# Power_Supplies.net
KiCad netlist of a schematic drawn in Altium Designer
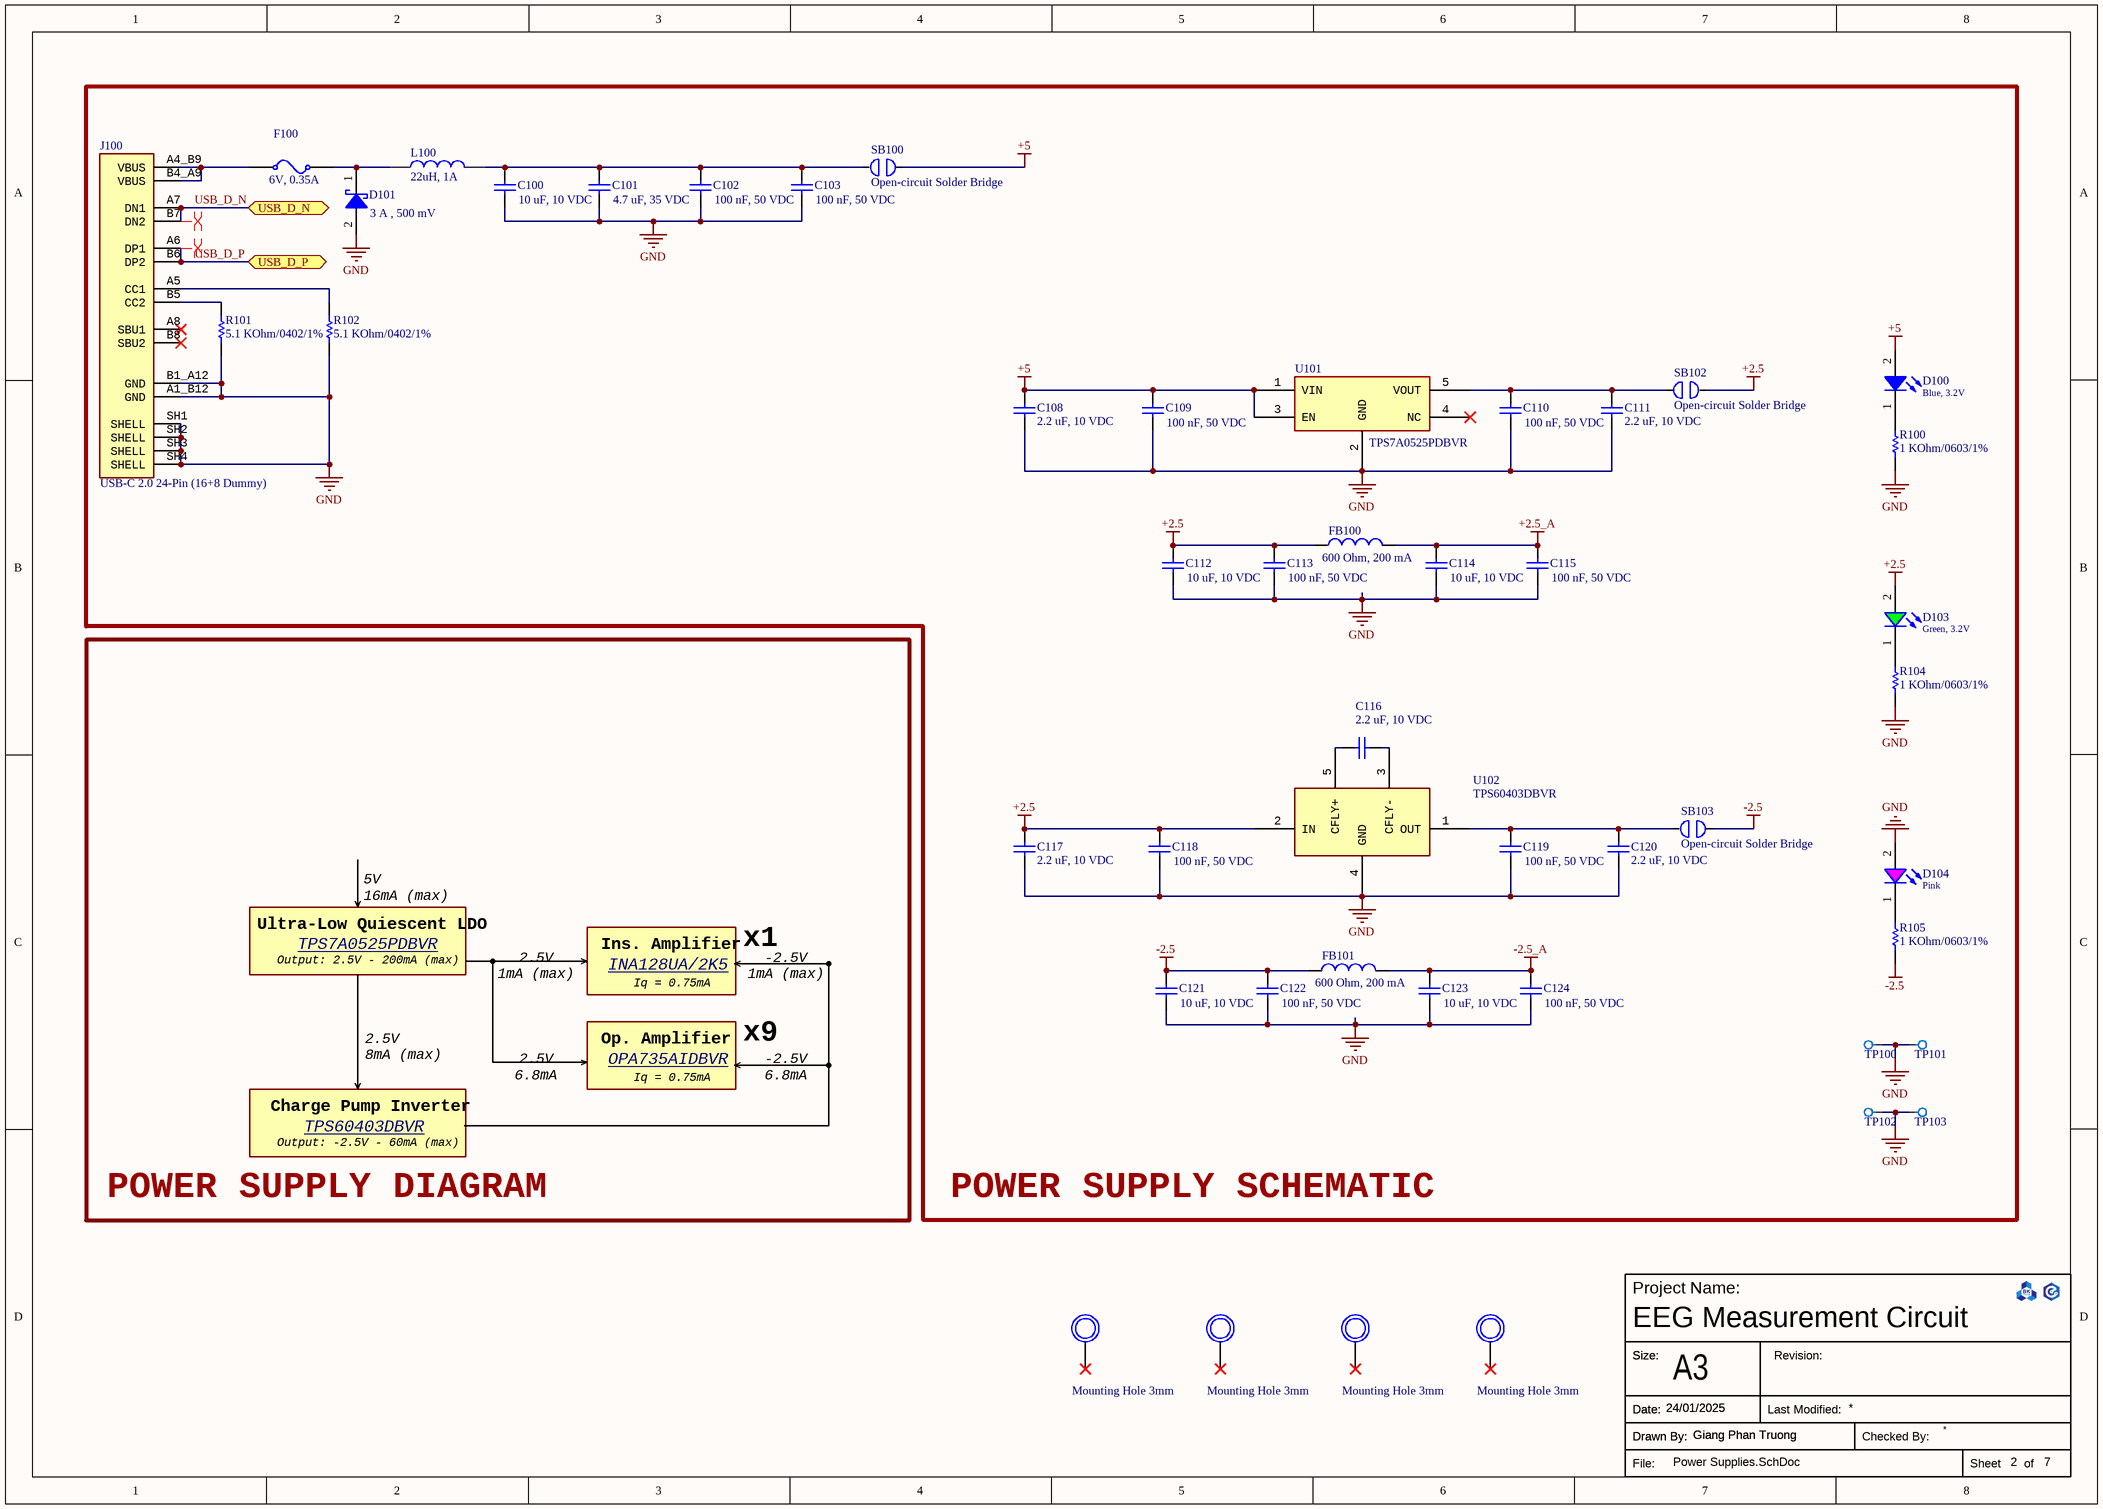
[diagram p0: Power Supplies.SchDoc]

(export (version "E")
  (design (tool "Eeschema 10.0.6"))
  (components
    (comp (ref "C100")
      (value "10 uF, 10 VDC")
      (footprint "CAP_0603")
      (description "CAP, size 0603, 10 uF, 10 VDC")
      (fields (field (name "TOLERANCE") "+/-10%"))
      (libsource (lib "Altium_Ceramic_Cap") (part "0106031061010"))
    )
    (comp (ref "C101")
      (value "4.7 uF, 35 VDC")
      (footprint "CAP_0603")
      (description "CAP, size 0603, 4.7 uF, 35 VDC")
      (fields (field (name "TOLERANCE") "+/-10%"))
      (libsource (lib "Altium_Ceramic_Cap") (part "0106034751035"))
    )
    (comp (ref "C102")
      (value "100 nF, 50 VDC")
      (footprint "CAP_0603")
      (description "CAP, size 0603, 100 nF, 50 VDC")
      (fields (field (name "TOLERANCE") "+/-10%"))
      (libsource (lib "Altium_Ceramic_Cap") (part "0106031041050"))
    )
    (comp (ref "C103")
      (value "100 nF, 50 VDC")
      (footprint "CAP_0603")
      (description "CAP, size 0603, 100 nF, 50 VDC")
      (fields (field (name "TOLERANCE") "+/-10%"))
      (libsource (lib "Altium_Ceramic_Cap") (part "0106031041050"))
    )
    (comp (ref "C108")
      (value "2.2 uF, 10 VDC")
      (footprint "CAP_0603")
      (description "CAP, size 0603, 2.2 uF, 10 VDC")
      (fields (field (name "TOLERANCE") "+/-10%"))
      (libsource (lib "Altium_Ceramic_Cap") (part "0106032251010"))
    )
    (comp (ref "C109")
      (value "100 nF, 50 VDC")
      (footprint "CAP_0603")
      (description "CAP, size 0603, 100 nF, 50 VDC")
      (fields (field (name "TOLERANCE") "+/-10%"))
      (libsource (lib "Altium_Ceramic_Cap") (part "0106031041050"))
    )
    (comp (ref "C110")
      (value "100 nF, 50 VDC")
      (footprint "CAP_0603")
      (description "CAP, size 0603, 100 nF, 50 VDC")
      (fields (field (name "TOLERANCE") "+/-10%"))
      (libsource (lib "Altium_Ceramic_Cap") (part "0106031041050"))
    )
    (comp (ref "C111")
      (value "2.2 uF, 10 VDC")
      (footprint "CAP_0603")
      (description "CAP, size 0603, 2.2 uF, 10 VDC")
      (fields (field (name "TOLERANCE") "+/-10%"))
      (libsource (lib "Altium_Ceramic_Cap") (part "0106032251010"))
    )
    (comp (ref "C112")
      (value "10 uF, 10 VDC")
      (footprint "CAP_0603")
      (description "CAP, size 0603, 10 uF, 10 VDC")
      (fields (field (name "TOLERANCE") "+/-10%"))
      (libsource (lib "Altium_Ceramic_Cap") (part "0106031061010"))
    )
    (comp (ref "C113")
      (value "100 nF, 50 VDC")
      (footprint "CAP_0603")
      (description "CAP, size 0603, 100 nF, 50 VDC")
      (fields (field (name "TOLERANCE") "+/-10%"))
      (libsource (lib "Altium_Ceramic_Cap") (part "0106031041050"))
    )
    (comp (ref "C114")
      (value "10 uF, 10 VDC")
      (footprint "CAP_0603")
      (description "CAP, size 0603, 10 uF, 10 VDC")
      (fields (field (name "TOLERANCE") "+/-10%"))
      (libsource (lib "Altium_Ceramic_Cap") (part "0106031061010"))
    )
    (comp (ref "C115")
      (value "100 nF, 50 VDC")
      (footprint "CAP_0603")
      (description "CAP, size 0603, 100 nF, 50 VDC")
      (fields (field (name "TOLERANCE") "+/-10%"))
      (libsource (lib "Altium_Ceramic_Cap") (part "0106031041050"))
    )
    (comp (ref "C116")
      (value "2.2 uF, 10 VDC")
      (footprint "CAP_0603")
      (description "CAP, size 0603, 2.2 uF, 10 VDC")
      (fields (field (name "TOLERANCE") "+/-10%"))
      (libsource (lib "Altium_Ceramic_Cap") (part "0106032251010"))
    )
    (comp (ref "C117")
      (value "2.2 uF, 10 VDC")
      (footprint "CAP_0603")
      (description "CAP, size 0603, 2.2 uF, 10 VDC")
      (fields (field (name "TOLERANCE") "+/-10%"))
      (libsource (lib "Altium_Ceramic_Cap") (part "0106032251010"))
    )
    (comp (ref "C118")
      (value "100 nF, 50 VDC")
      (footprint "CAP_0603")
      (description "CAP, size 0603, 100 nF, 50 VDC")
      (fields (field (name "TOLERANCE") "+/-10%"))
      (libsource (lib "Altium_Ceramic_Cap") (part "0106031041050"))
    )
    (comp (ref "C119")
      (value "100 nF, 50 VDC")
      (footprint "CAP_0603")
      (description "CAP, size 0603, 100 nF, 50 VDC")
      (fields (field (name "TOLERANCE") "+/-10%"))
      (libsource (lib "Altium_Ceramic_Cap") (part "0106031041050"))
    )
    (comp (ref "C120")
      (value "2.2 uF, 10 VDC")
      (footprint "CAP_0603")
      (description "CAP, size 0603, 2.2 uF, 10 VDC")
      (fields (field (name "TOLERANCE") "+/-10%"))
      (libsource (lib "Altium_Ceramic_Cap") (part "0106032251010"))
    )
    (comp (ref "C121")
      (value "10 uF, 10 VDC")
      (footprint "CAP_0603")
      (description "CAP, size 0603, 10 uF, 10 VDC")
      (fields (field (name "TOLERANCE") "+/-10%"))
      (libsource (lib "Altium_Ceramic_Cap") (part "0106031061010"))
    )
    (comp (ref "C122")
      (value "100 nF, 50 VDC")
      (footprint "CAP_0603")
      (description "CAP, size 0603, 100 nF, 50 VDC")
      (fields (field (name "TOLERANCE") "+/-10%"))
      (libsource (lib "Altium_Ceramic_Cap") (part "0106031041050"))
    )
    (comp (ref "C123")
      (value "10 uF, 10 VDC")
      (footprint "CAP_0603")
      (description "CAP, size 0603, 10 uF, 10 VDC")
      (fields (field (name "TOLERANCE") "+/-10%"))
      (libsource (lib "Altium_Ceramic_Cap") (part "0106031061010"))
    )
    (comp (ref "C124")
      (value "100 nF, 50 VDC")
      (footprint "CAP_0603")
      (description "CAP, size 0603, 100 nF, 50 VDC")
      (fields (field (name "TOLERANCE") "+/-10%"))
      (libsource (lib "Altium_Ceramic_Cap") (part "0106031041050"))
    )
    (comp (ref "D100")
      (value "Blue, 3.2V")
      (footprint "WL-SMCW_0603_H=0.7mm")
      (description "WL-SMCW SMT Mono-color Chip LED Blur, size 0603, Blue, 3.2V, 140deg")
      (libsource (lib "Altium_LED") (part "160603BlueBlur"))
    )
    (comp (ref "D101")
      (value "3 A , 500 mV")
      (footprint "SMC (DO-214AB)")
      (description "Schottky Diodes & Rectifiers 3.0 Amp 40 Volt")
      (fields
        (field (name "MANUFACTURER") "Vishay Semiconductors")
        (field (name "MANUFACTURER PART NUMBER") "SS34-E3/57T")
      )
      (libsource (lib "Altium_Diode") (part "SS34"))
    )
    (comp (ref "D103")
      (value "Green, 3.2V")
      (footprint "WL-SMCW_0603_H=0.7mm")
      (description "WL-SMCW SMT Mono-color Chip LED Blur, size 0603, Green, 3.2V, 140deg")
      (libsource (lib "Altium_LED") (part "160603GreenBlur"))
    )
    (comp (ref "D104")
      (value "Pink")
      (footprint "WL-SMCW_0603_H=0.7mm")
      (description "WL-SMCW SMT Mono-color Chip LED Blur, size 0603, Pink")
      (libsource (lib "Altium_LED") (part "160603PinkBlur"))
    )
    (comp (ref "F100")
      (value "6V, 0.35A")
      (footprint "Fuse_SMD_1206")
      (description "Resettable Fuse, Size 1206, 6V, 0.35A")
      (fields (field (name "MANUFACTURER") "Bourns"))
      (libsource (lib "Altium_Fuse") (part "061206035006"))
    )
    (comp (ref "FB100")
      (value "600 Ohm, 200 mA")
      (footprint "FER_0603")
      (description "Ferrite, 0603, 600 Ohms, 200 mA")
      (fields (field (name "TOLERANCE") "+/-25%"))
      (libsource (lib "Altium_Ferrite_Bead") (part "03060360120125"))
    )
    (comp (ref "FB101")
      (value "600 Ohm, 200 mA")
      (footprint "FER_0603")
      (description "Ferrite, 0603, 600 Ohms, 200 mA")
      (fields (field (name "TOLERANCE") "+/-25%"))
      (libsource (lib "Altium_Ferrite_Bead") (part "03060360120125"))
    )
    (comp (ref "H100")
      (value "Mounting Hole 3mm")
      (footprint "3mm with via")
      (libsource (lib "Altium_Mech") (part "Mounting Hole 3mm"))
    )
    (comp (ref "H101")
      (value "Mounting Hole 3mm")
      (footprint "3mm with via")
      (libsource (lib "Altium_Mech") (part "Mounting Hole 3mm"))
    )
    (comp (ref "H102")
      (value "Mounting Hole 3mm")
      (footprint "3mm with via")
      (libsource (lib "Altium_Mech") (part "Mounting Hole 3mm"))
    )
    (comp (ref "H103")
      (value "Mounting Hole 3mm")
      (footprint "3mm with via")
      (libsource (lib "Altium_Mech") (part "Mounting Hole 3mm"))
    )
    (comp (ref "J100")
      (value "USB-C 2.0 24-Pin (16+8 Dummy)")
      (footprint "GCT_USB4105-GF-A")
      (fields (field (name "MF") "{'manufacturer': u'GCT'}") (field (name "MP") "USB4105-GF-A"))
      (libsource (lib "Giang_USB") (part "USB4105-GF-A"))
    )
    (comp (ref "L100")
      (value "22uH, 1A")
      (footprint "Inductor_CDRH4D28")
      (description "22uH 20% 1A SMD Power Inductor 4.8x4.8x2.8 mm")
      (libsource (lib "Giang_Inductor") (part "IND_22uH_4D28"))
    )
    (comp (ref "R100")
      (value "1 KOhm/0603/1%")
      (footprint "R0603")
      (description "Code 102, 1/10W")
      (fields (field (name "Comment") "Resistor 1 KOhm 0603 1%"))
      (libsource (lib "Giang_Resistor") (part "Resistor 1 KOhm 0603 1%"))
    )
    (comp (ref "R101")
      (value "5.1 KOhm/0402/1%")
      (footprint "R0402")
      (description "RC0402FR-135K1L")
      (fields (field (name "Comment") "Resistor 5.1 KOhm 0402"))
      (libsource (lib "Giang_Resistor") (part "Resistor 5.1 KOhm 0402"))
    )
    (comp (ref "R102")
      (value "5.1 KOhm/0402/1%")
      (footprint "R0402")
      (description "RC0402FR-135K1L")
      (fields (field (name "Comment") "Resistor 5.1 KOhm 0402"))
      (libsource (lib "Giang_Resistor") (part "Resistor 5.1 KOhm 0402"))
    )
    (comp (ref "R104")
      (value "1 KOhm/0603/1%")
      (footprint "R0603")
      (description "Code 102, 1/10W")
      (fields (field (name "Comment") "Resistor 1 KOhm 0603 1%"))
      (libsource (lib "Giang_Resistor") (part "Resistor 1 KOhm 0603 1%"))
    )
    (comp (ref "R105")
      (value "1 KOhm/0603/1%")
      (footprint "R0603")
      (description "Code 102, 1/10W")
      (fields (field (name "Comment") "Resistor 1 KOhm 0603 1%"))
      (libsource (lib "Giang_Resistor") (part "Resistor 1 KOhm 0603 1%"))
    )
    (comp (ref "SB100")
      (value "Open-circuit Solder Bridge")
      (footprint "SolderBridgeOpen")
      (libsource (lib "Giang's Libs") (part "Open-circuit Solder Bridge"))
    )
    (comp (ref "SB102")
      (value "Open-circuit Solder Bridge")
      (footprint "SolderBridgeOpen")
      (libsource (lib "Giang's Libs") (part "Open-circuit Solder Bridge"))
    )
    (comp (ref "SB103")
      (value "Open-circuit Solder Bridge")
      (footprint "SolderBridgeOpen")
      (libsource (lib "Giang's Libs") (part "Open-circuit Solder Bridge"))
    )
    (comp (ref "TP100")
      (value "Testpoint_SMD")
      (footprint "TestPoint_Pad_3.0x3.0mm")
      (libsource (lib "BluetoothTracking") (part "Testpoint_SMD"))
    )
    (comp (ref "TP101")
      (value "Testpoint_SMD")
      (footprint "TestPoint_Pad_3.0x3.0mm")
      (libsource (lib "BluetoothTracking") (part "Testpoint_SMD"))
    )
    (comp (ref "TP102")
      (value "Testpoint_SMD")
      (footprint "TestPoint_Pad_3.0x3.0mm")
      (libsource (lib "BluetoothTracking") (part "Testpoint_SMD"))
    )
    (comp (ref "TP103")
      (value "Testpoint_SMD")
      (footprint "TestPoint_Pad_3.0x3.0mm")
      (libsource (lib "BluetoothTracking") (part "Testpoint_SMD"))
    )
    (comp (ref "U101")
      (value "TPS7A0525PDBVR")
      (footprint "DBV0005A_L")
      (description "Linear Voltage Regulator IC Positive Fixed 1 Output 200mA SOT-23-5")
      (libsource (lib "Giang_Power-IC") (part "TPS7A0525PDBVR"))
    )
    (comp (ref "U102")
      (value "TPS60403DBVR")
      (footprint "SOT95P280X145-5N")
      (description "60mA Charge Pump Voltage Inverter with Fixed 250kHz Operation")
      (fields (field (name "MF") "Texas Instruments"))
      (libsource (lib "Giang_Power-IC") (part "TPS60403DBVR"))
    )
  )
  (nets
    (net (code "1") (name "+2.5") (class "Default")
      (node (ref "C112") (pin "2") (pinfunction "2_2") (pintype "passive"))
      (node (ref "C113") (pin "2") (pinfunction "2_2") (pintype "passive"))
      (node (ref "C117") (pin "2") (pinfunction "2_2") (pintype "passive"))
      (node (ref "C118") (pin "2") (pinfunction "2_2") (pintype "passive"))
      (node (ref "D103") (pin "2") (pinfunction "A_2") (pintype "passive"))
      (node (ref "FB100") (pin "1") (pinfunction "1_1") (pintype "passive"))
      (node (ref "SB102") (pin "1") (pinfunction "1_1") (pintype "passive"))
      (node (ref "U102") (pin "2") (pinfunction "IN_2") (pintype "passive"))
    )
    (net (code "2") (name "+2.5_A") (class "Default")
      (node (ref "C114") (pin "2") (pinfunction "2_2") (pintype "passive"))
      (node (ref "C115") (pin "2") (pinfunction "2_2") (pintype "passive"))
      (node (ref "FB100") (pin "2") (pinfunction "2_2") (pintype "passive"))
    )
    (net (code "3") (name "+5") (class "Default")
      (node (ref "C108") (pin "2") (pinfunction "2_2") (pintype "passive"))
      (node (ref "C109") (pin "2") (pinfunction "2_2") (pintype "passive"))
      (node (ref "D100") (pin "2") (pinfunction "A_2") (pintype "passive"))
      (node (ref "SB100") (pin "1") (pinfunction "1_1") (pintype "passive"))
      (node (ref "U101") (pin "1") (pinfunction "VIN_1") (pintype "passive"))
      (node (ref "U101") (pin "3") (pinfunction "EN_3") (pintype "passive"))
    )
    (net (code "4") (name "-2.5") (class "Default")
      (node (ref "C121") (pin "2") (pinfunction "2_2") (pintype "passive"))
      (node (ref "C122") (pin "2") (pinfunction "2_2") (pintype "passive"))
      (node (ref "FB101") (pin "1") (pinfunction "1_1") (pintype "passive"))
      (node (ref "R105") (pin "2") (pinfunction "2_2") (pintype "passive"))
      (node (ref "SB103") (pin "1") (pinfunction "1_1") (pintype "passive"))
    )
    (net (code "5") (name "-2.5_A") (class "Default")
      (node (ref "C123") (pin "2") (pinfunction "2_2") (pintype "passive"))
      (node (ref "C124") (pin "2") (pinfunction "2_2") (pintype "passive"))
      (node (ref "FB101") (pin "2") (pinfunction "2_2") (pintype "passive"))
    )
    (net (code "6") (name "/USB_D_N") (class "Default")
      (node (ref "J100") (pin "A7") (pinfunction "DN1_A7") (pintype "passive"))
      (node (ref "J100") (pin "B7") (pinfunction "DN2_B7") (pintype "passive"))
    )
    (net (code "7") (name "/USB_D_P") (class "Default")
      (node (ref "J100") (pin "A6") (pinfunction "DP1_A6") (pintype "passive"))
      (node (ref "J100") (pin "B6") (pinfunction "DP2_B6") (pintype "passive"))
    )
    (net (code "8") (name "GND") (class "Default")
      (node (ref "C100") (pin "1") (pinfunction "1_1") (pintype "passive"))
      (node (ref "C101") (pin "1") (pinfunction "1_1") (pintype "passive"))
      (node (ref "C102") (pin "1") (pinfunction "1_1") (pintype "passive"))
      (node (ref "C103") (pin "1") (pinfunction "1_1") (pintype "passive"))
      (node (ref "C108") (pin "1") (pinfunction "1_1") (pintype "passive"))
      (node (ref "C109") (pin "1") (pinfunction "1_1") (pintype "passive"))
      (node (ref "C110") (pin "1") (pinfunction "1_1") (pintype "passive"))
      (node (ref "C111") (pin "1") (pinfunction "1_1") (pintype "passive"))
      (node (ref "C112") (pin "1") (pinfunction "1_1") (pintype "passive"))
      (node (ref "C113") (pin "1") (pinfunction "1_1") (pintype "passive"))
      (node (ref "C114") (pin "1") (pinfunction "1_1") (pintype "passive"))
      (node (ref "C115") (pin "1") (pinfunction "1_1") (pintype "passive"))
      (node (ref "C117") (pin "1") (pinfunction "1_1") (pintype "passive"))
      (node (ref "C118") (pin "1") (pinfunction "1_1") (pintype "passive"))
      (node (ref "C119") (pin "1") (pinfunction "1_1") (pintype "passive"))
      (node (ref "C120") (pin "1") (pinfunction "1_1") (pintype "passive"))
      (node (ref "C121") (pin "1") (pinfunction "1_1") (pintype "passive"))
      (node (ref "C122") (pin "1") (pinfunction "1_1") (pintype "passive"))
      (node (ref "C123") (pin "1") (pinfunction "1_1") (pintype "passive"))
      (node (ref "C124") (pin "1") (pinfunction "1_1") (pintype "passive"))
      (node (ref "D101") (pin "2") (pinfunction "A_2") (pintype "passive"))
      (node (ref "D104") (pin "2") (pinfunction "A_2") (pintype "passive"))
      (node (ref "J100") (pin "A1_B12") (pinfunction "GND_A1_B12") (pintype "passive"))
      (node (ref "J100") (pin "B1_A12") (pinfunction "GND_B1_A12") (pintype "passive"))
      (node (ref "J100") (pin "SH1") (pinfunction "SHELL_SH1") (pintype "passive"))
      (node (ref "J100") (pin "SH2") (pinfunction "SHELL_SH2") (pintype "passive"))
      (node (ref "J100") (pin "SH3") (pinfunction "SHELL_SH3") (pintype "passive"))
      (node (ref "J100") (pin "SH4") (pinfunction "SHELL_SH4") (pintype "passive"))
      (node (ref "R100") (pin "2") (pinfunction "2_2") (pintype "passive"))
      (node (ref "R101") (pin "1") (pinfunction "1_1") (pintype "passive"))
      (node (ref "R102") (pin "1") (pinfunction "1_1") (pintype "passive"))
      (node (ref "R104") (pin "2") (pinfunction "2_2") (pintype "passive"))
      (node (ref "TP100") (pin "1") (pinfunction "1_1") (pintype "passive"))
      (node (ref "TP101") (pin "1") (pinfunction "1_1") (pintype "passive"))
      (node (ref "TP102") (pin "1") (pinfunction "1_1") (pintype "passive"))
      (node (ref "TP103") (pin "1") (pinfunction "1_1") (pintype "passive"))
      (node (ref "U101") (pin "2") (pinfunction "GND_2") (pintype "passive"))
      (node (ref "U102") (pin "4") (pinfunction "GND_4") (pintype "passive"))
    )
    (net (code "9") (name "Net-(C100-Pad2)") (class "Default")
      (node (ref "C100") (pin "2") (pinfunction "2_2") (pintype "passive"))
      (node (ref "C101") (pin "2") (pinfunction "2_2") (pintype "passive"))
      (node (ref "C102") (pin "2") (pinfunction "2_2") (pintype "passive"))
      (node (ref "C103") (pin "2") (pinfunction "2_2") (pintype "passive"))
      (node (ref "L100") (pin "2") (pinfunction "2_2") (pintype "passive"))
      (node (ref "SB100") (pin "2") (pinfunction "2_2") (pintype "passive"))
    )
    (net (code "10") (name "Net-(D100-K)") (class "Default")
      (node (ref "D100") (pin "1") (pinfunction "K_1") (pintype "passive"))
      (node (ref "R100") (pin "1") (pinfunction "1_1") (pintype "passive"))
    )
    (net (code "11") (name "Net-(D101-K)") (class "Default")
      (node (ref "D101") (pin "1") (pinfunction "K_1") (pintype "passive"))
      (node (ref "F100") (pin "1") (pinfunction "1_1") (pintype "passive"))
      (node (ref "L100") (pin "1") (pinfunction "1_1") (pintype "passive"))
    )
    (net (code "12") (name "Net-(D103-K)") (class "Default")
      (node (ref "D103") (pin "1") (pinfunction "K_1") (pintype "passive"))
      (node (ref "R104") (pin "1") (pinfunction "1_1") (pintype "passive"))
    )
    (net (code "13") (name "Net-(D104-K)") (class "Default")
      (node (ref "D104") (pin "1") (pinfunction "K_1") (pintype "passive"))
      (node (ref "R105") (pin "1") (pinfunction "1_1") (pintype "passive"))
    )
    (net (code "14") (name "Net-(F100-Pad0)") (class "Default")
      (node (ref "F100") (pin "0") (pinfunction "0_0") (pintype "passive"))
      (node (ref "J100") (pin "A4_B9") (pinfunction "VBUS_A4_B9") (pintype "passive"))
      (node (ref "J100") (pin "B4_A9") (pinfunction "VBUS_B4_A9") (pintype "passive"))
    )
    (net (code "15") (name "Net-(J100-CC1)") (class "Default")
      (node (ref "J100") (pin "A5") (pinfunction "CC1_A5") (pintype "passive"))
      (node (ref "R102") (pin "2") (pinfunction "2_2") (pintype "passive"))
    )
    (net (code "16") (name "Net-(J100-CC2)") (class "Default")
      (node (ref "J100") (pin "B5") (pinfunction "CC2_B5") (pintype "passive"))
      (node (ref "R101") (pin "2") (pinfunction "2_2") (pintype "passive"))
    )
    (net (code "17") (name "Net-(U101-VOUT)") (class "Default")
      (node (ref "C110") (pin "2") (pinfunction "2_2") (pintype "passive"))
      (node (ref "C111") (pin "2") (pinfunction "2_2") (pintype "passive"))
      (node (ref "SB102") (pin "2") (pinfunction "2_2") (pintype "passive"))
      (node (ref "U101") (pin "5") (pinfunction "VOUT_5") (pintype "passive"))
    )
    (net (code "18") (name "Net-(U102-CFLY+)") (class "Default")
      (node (ref "C116") (pin "2") (pinfunction "2_2") (pintype "passive"))
      (node (ref "U102") (pin "5") (pinfunction "CFLY+_5") (pintype "passive"))
    )
    (net (code "19") (name "Net-(U102-CFLY-)") (class "Default")
      (node (ref "C116") (pin "1") (pinfunction "1_1") (pintype "passive"))
      (node (ref "U102") (pin "3") (pinfunction "CFLY-_3") (pintype "passive"))
    )
    (net (code "20") (name "Net-(U102-OUT)") (class "Default")
      (node (ref "C119") (pin "2") (pinfunction "2_2") (pintype "passive"))
      (node (ref "C120") (pin "2") (pinfunction "2_2") (pintype "passive"))
      (node (ref "SB103") (pin "2") (pinfunction "2_2") (pintype "passive"))
      (node (ref "U102") (pin "1") (pinfunction "OUT_1") (pintype "passive"))
    )
    (net (code "21") (name "unconnected-(H100-Pad0)") (class "Default")
      (node (ref "H100") (pin "0") (pinfunction "0_0") (pintype "passive"))
    )
    (net (code "22") (name "unconnected-(H101-Pad0)") (class "Default")
      (node (ref "H101") (pin "0") (pinfunction "0_0") (pintype "passive"))
    )
    (net (code "23") (name "unconnected-(H102-Pad0)") (class "Default")
      (node (ref "H102") (pin "0") (pinfunction "0_0") (pintype "passive"))
    )
    (net (code "24") (name "unconnected-(H103-Pad0)") (class "Default")
      (node (ref "H103") (pin "0") (pinfunction "0_0") (pintype "passive"))
    )
    (net (code "25") (name "unconnected-(J100-SBU1-PadA8)") (class "Default")
      (node (ref "J100") (pin "A8") (pinfunction "SBU1_A8") (pintype "passive+no_connect"))
    )
    (net (code "26") (name "unconnected-(J100-SBU2-PadB8)") (class "Default")
      (node (ref "J100") (pin "B8") (pinfunction "SBU2_B8") (pintype "passive+no_connect"))
    )
    (net (code "27") (name "unconnected-(U101-NC-Pad4)") (class "Default")
      (node (ref "U101") (pin "4") (pinfunction "NC_4") (pintype "passive+no_connect"))
    )
  )
)
